# frontend_v1.net
KiCad netlist of a schematic drawn in EAGLE
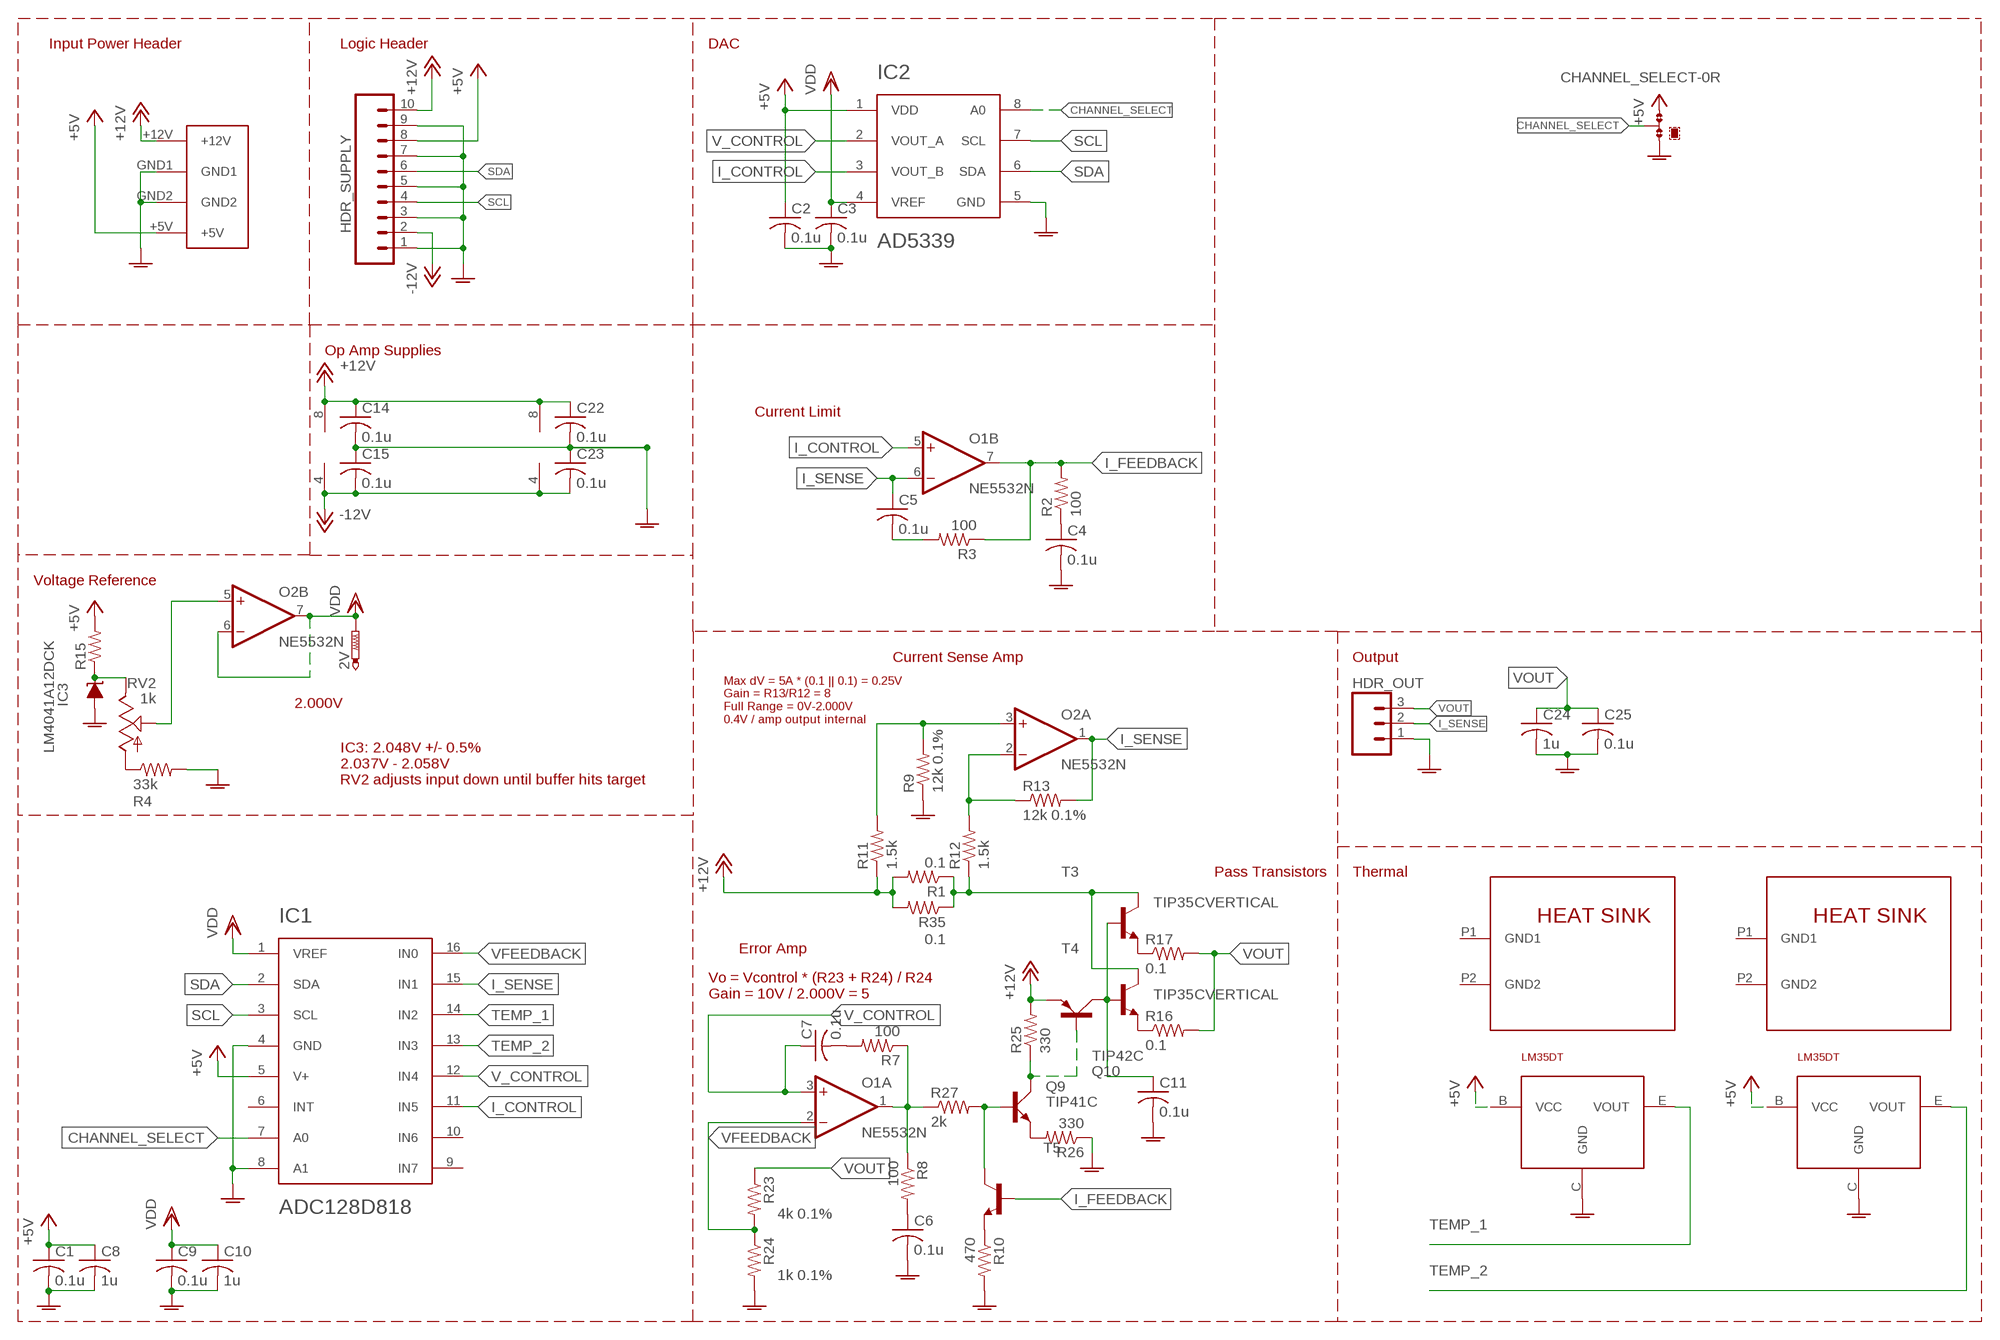
[diagram p0: schematic, sheet 1]

(export (version "E")
  (design (tool "Eeschema 10.0.6"))
  (components
    (comp (ref "2V")
      (value "PTR1PAD1-17")
      (footprint "eagle-import:P1-17")
      (libsource (lib "eagle-import") (part "PTR1PAD1-17"))
    )
    (comp (ref "C1")
      (value "0.1u")
      (footprint "eagle-import:C0805")
      (libsource (lib "eagle-import") (part "C-USC0805"))
    )
    (comp (ref "C2")
      (value "0.1u")
      (footprint "eagle-import:C0805")
      (libsource (lib "eagle-import") (part "C-USC0805"))
    )
    (comp (ref "C3")
      (value "0.1u")
      (footprint "eagle-import:C0805")
      (libsource (lib "eagle-import") (part "C-USC0805"))
    )
    (comp (ref "C4")
      (value "0.1u")
      (footprint "eagle-import:C0805")
      (libsource (lib "eagle-import") (part "C-USC0805"))
    )
    (comp (ref "C5")
      (value "0.1u")
      (footprint "eagle-import:C0805")
      (libsource (lib "eagle-import") (part "C-USC0805"))
    )
    (comp (ref "C6")
      (value "0.1u")
      (footprint "eagle-import:C0805")
      (libsource (lib "eagle-import") (part "C-USC0805"))
    )
    (comp (ref "C7")
      (value "0.1u")
      (footprint "eagle-import:C0805")
      (libsource (lib "eagle-import") (part "C-USC0805"))
    )
    (comp (ref "C8")
      (value "1u")
      (footprint "eagle-import:C0805")
      (libsource (lib "eagle-import") (part "C-USC0805"))
    )
    (comp (ref "C9")
      (value "0.1u")
      (footprint "eagle-import:C0805")
      (libsource (lib "eagle-import") (part "C-USC0805"))
    )
    (comp (ref "C10")
      (value "1u")
      (footprint "eagle-import:C0805")
      (libsource (lib "eagle-import") (part "C-USC0805"))
    )
    (comp (ref "C11")
      (value "0.1u")
      (footprint "eagle-import:C0805")
      (libsource (lib "eagle-import") (part "C-USC0805"))
    )
    (comp (ref "C14")
      (value "0.1u")
      (footprint "eagle-import:C0805")
      (libsource (lib "eagle-import") (part "C-USC0805"))
    )
    (comp (ref "C15")
      (value "0.1u")
      (footprint "eagle-import:C0805")
      (libsource (lib "eagle-import") (part "C-USC0805"))
    )
    (comp (ref "C22")
      (value "0.1u")
      (footprint "eagle-import:C0805")
      (libsource (lib "eagle-import") (part "C-USC0805"))
    )
    (comp (ref "C23")
      (value "0.1u")
      (footprint "eagle-import:C0805")
      (libsource (lib "eagle-import") (part "C-USC0805"))
    )
    (comp (ref "C24")
      (value "1u")
      (footprint "eagle-import:C1206")
      (libsource (lib "eagle-import") (part "C-USC1206"))
    )
    (comp (ref "C25")
      (value "0.1u")
      (footprint "eagle-import:C1206")
      (libsource (lib "eagle-import") (part "C-USC1206"))
    )
    (comp (ref "CHANNEL_SELECT")
      (value "0R-JUMPA")
      (footprint "eagle-import:A0R-JMP")
      (libsource (lib "eagle-import") (part "0R-JUMPA"))
    )
    (comp (ref "HDR_OUT")
      (value "M03")
      (footprint "eagle-import:03P")
      (libsource (lib "eagle-import") (part "M03"))
    )
    (comp (ref "HDR_SUPPLY")
      (value "M10")
      (footprint "eagle-import:10P")
      (libsource (lib "eagle-import") (part "M10"))
    )
    (comp (ref "IC1")
      (value "ADC128D818")
      (footprint "eagle-import:TSSOP16")
      (libsource (lib "eagle-import") (part "ADC128D818"))
    )
    (comp (ref "IC2")
      (value "AD5339MSOP8")
      (footprint "eagle-import:MSOP08")
      (libsource (lib "eagle-import") (part "AD5339MSOP8"))
    )
    (comp (ref "IC3")
      (value "LM4041A12DCK")
      (footprint "eagle-import:DCK_R-PDSO-G5")
      (fields (field (name "MPN") "LM4041A12IDCKR"))
      (libsource (lib "eagle-import") (part "LM4041DCKA12"))
    )
    (comp (ref "O1")
      (value "NE5532N")
      (footprint "eagle-import:DIL08")
      (libsource (lib "eagle-import") (part "NE5532N"))
    )
    (comp (ref "O2")
      (value "NE5532N")
      (footprint "eagle-import:DIL08")
      (libsource (lib "eagle-import") (part "NE5532N"))
    )
    (comp (ref "Q9")
      (value "TIP41C")
      (footprint "eagle-import:TO220AV")
      (libsource (lib "eagle-import") (part "TIP41C"))
    )
    (comp (ref "Q10")
      (value "TIP42C")
      (footprint "eagle-import:TO220AV")
      (libsource (lib "eagle-import") (part "TIP42C"))
    )
    (comp (ref "R1")
      (value "0.1")
      (footprint "eagle-import:R2512")
      (libsource (lib "eagle-import") (part "R-US_R2512"))
    )
    (comp (ref "R2")
      (value "100")
      (footprint "eagle-import:M0805")
      (libsource (lib "eagle-import") (part "R-US_M0805"))
    )
    (comp (ref "R3")
      (value "100")
      (footprint "eagle-import:M0805")
      (libsource (lib "eagle-import") (part "R-US_M0805"))
    )
    (comp (ref "R4")
      (value "33k")
      (footprint "eagle-import:M0805")
      (libsource (lib "eagle-import") (part "R-US_M0805"))
    )
    (comp (ref "R7")
      (value "100")
      (footprint "eagle-import:M0805")
      (libsource (lib "eagle-import") (part "R-US_M0805"))
    )
    (comp (ref "R8")
      (value "100")
      (footprint "eagle-import:M0805")
      (libsource (lib "eagle-import") (part "R-US_M0805"))
    )
    (comp (ref "R9")
      (value "12k 0.1%")
      (footprint "eagle-import:M0805")
      (libsource (lib "eagle-import") (part "R-US_M0805"))
    )
    (comp (ref "R10")
      (value "470")
      (footprint "eagle-import:M0805")
      (libsource (lib "eagle-import") (part "R-US_M0805"))
    )
    (comp (ref "R11")
      (value "1.5k")
      (footprint "eagle-import:M0805")
      (libsource (lib "eagle-import") (part "R-US_M0805"))
    )
    (comp (ref "R12")
      (value "1.5k")
      (footprint "eagle-import:M0805")
      (libsource (lib "eagle-import") (part "R-US_M0805"))
    )
    (comp (ref "R13")
      (value "12k 0.1%")
      (footprint "eagle-import:M0805")
      (libsource (lib "eagle-import") (part "R-US_M0805"))
    )
    (comp (ref "R15")
      (value "R-US_M0805")
      (footprint "eagle-import:M0805")
      (libsource (lib "eagle-import") (part "R-US_M0805"))
    )
    (comp (ref "R16")
      (value "0.1")
      (footprint "eagle-import:R2512")
      (libsource (lib "eagle-import") (part "R-US_R2512"))
    )
    (comp (ref "R17")
      (value "0.1")
      (footprint "eagle-import:R2512")
      (libsource (lib "eagle-import") (part "R-US_R2512"))
    )
    (comp (ref "R23")
      (value "4k 0.1%")
      (footprint "eagle-import:M0805")
      (libsource (lib "eagle-import") (part "R-US_M0805"))
    )
    (comp (ref "R24")
      (value "1k 0.1%")
      (footprint "eagle-import:M0805")
      (libsource (lib "eagle-import") (part "R-US_M0805"))
    )
    (comp (ref "R25")
      (value "330")
      (footprint "eagle-import:M0805")
      (libsource (lib "eagle-import") (part "R-US_M0805"))
    )
    (comp (ref "R26")
      (value "330")
      (footprint "eagle-import:M0805")
      (libsource (lib "eagle-import") (part "R-US_M0805"))
    )
    (comp (ref "R27")
      (value "2k")
      (footprint "eagle-import:M0805")
      (libsource (lib "eagle-import") (part "R-US_M0805"))
    )
    (comp (ref "R35")
      (value "0.1")
      (footprint "eagle-import:R2512")
      (libsource (lib "eagle-import") (part "R-US_R2512"))
    )
    (comp (ref "RV2")
      (value "1k")
      (footprint "eagle-import:TRIM_POT")
      (libsource (lib "eagle-import") (part "POTTRIM"))
    )
    (comp (ref "T3")
      (value "TIP35CVERTICAL")
      (footprint "eagle-import:TO247")
      (libsource (lib "eagle-import") (part "TIP35CVERTICAL"))
    )
    (comp (ref "T4")
      (value "TIP35CVERTICAL")
      (footprint "eagle-import:TO247")
      (libsource (lib "eagle-import") (part "TIP35CVERTICAL"))
    )
    (comp (ref "T5")
      (value "MMBT2222ALT1-NPN-SOT23-BEC")
      (footprint "eagle-import:SOT23-BEC")
      (libsource (lib "eagle-import") (part "-NPN-SOT23-BECMMBT2222ALT1"))
    )
    (comp (ref "U$1")
      (value "MOLEX-8981")
      (footprint "eagle-import:MOLEX-8981-MALE")
      (libsource (lib "eagle-import") (part "MOLEX-8981"))
    )
    (comp (ref "U$2")
      (value "FA-T220-X")
      (footprint "eagle-import:FA-T220-X")
      (libsource (lib "eagle-import") (part "FA-T220-X"))
    )
    (comp (ref "U$3")
      (value "FA-T220-X")
      (footprint "eagle-import:FA-T220-X")
      (libsource (lib "eagle-import") (part "FA-T220-X"))
    )
    (comp (ref "U2")
      (value "LM35DT")
      (footprint "eagle-import:TO220AV")
      (libsource (lib "eagle-import") (part "LM35DT"))
    )
    (comp (ref "U3")
      (value "LM35DT")
      (footprint "eagle-import:TO220AV")
      (libsource (lib "eagle-import") (part "LM35DT"))
    )
  )
  (nets
    (net (code "1") (name "+5V") (class "Default")
      (node (ref "C1") (pin "1") (pinfunction "1_1") (pintype "passive"))
      (node (ref "C2") (pin "1") (pinfunction "1_1") (pintype "passive"))
      (node (ref "C8") (pin "1") (pinfunction "1_1") (pintype "passive"))
      (node (ref "CHANNEL_SELECT") (pin "3") (pinfunction "3_3") (pintype "passive"))
      (node (ref "HDR_SUPPLY") (pin "8") (pinfunction "8_8") (pintype "passive"))
      (node (ref "IC1") (pin "5") (pinfunction "V+_5") (pintype "bidirectional"))
      (node (ref "IC2") (pin "1") (pinfunction "VDD_1") (pintype "bidirectional"))
      (node (ref "R15") (pin "2") (pinfunction "2_2") (pintype "passive"))
      (node (ref "U$1") (pin "+5V") (pinfunction "+5V_+5V") (pintype "bidirectional"))
      (node (ref "U2") (pin "B") (pinfunction "VCC_B") (pintype "bidirectional"))
      (node (ref "U3") (pin "B") (pinfunction "VCC_B") (pintype "bidirectional"))
    )
    (net (code "2") (name "+12V") (class "Default")
      (node (ref "C14") (pin "1") (pinfunction "1_1") (pintype "passive"))
      (node (ref "C22") (pin "1") (pinfunction "1_1") (pintype "passive"))
      (node (ref "HDR_SUPPLY") (pin "10") (pinfunction "10_10") (pintype "passive"))
      (node (ref "O1") (pin "8") (pinfunction "V+_8") (pintype "power_in"))
      (node (ref "O2") (pin "8") (pinfunction "V+_8") (pintype "power_in"))
      (node (ref "Q10") (pin "E") (pinfunction "E_E") (pintype "passive"))
      (node (ref "R1") (pin "2") (pinfunction "2_2") (pintype "passive"))
      (node (ref "R11") (pin "1") (pinfunction "1_1") (pintype "passive"))
      (node (ref "R25") (pin "2") (pinfunction "2_2") (pintype "passive"))
      (node (ref "R35") (pin "2") (pinfunction "2_2") (pintype "passive"))
      (node (ref "U$1") (pin "+12V") (pinfunction "+12V_+12V") (pintype "bidirectional"))
    )
    (net (code "3") (name "-12V") (class "Default")
      (node (ref "C15") (pin "2") (pinfunction "2_2") (pintype "passive"))
      (node (ref "C23") (pin "2") (pinfunction "2_2") (pintype "passive"))
      (node (ref "HDR_SUPPLY") (pin "2") (pinfunction "2_2") (pintype "passive"))
      (node (ref "O1") (pin "4") (pinfunction "V-_4") (pintype "power_in"))
      (node (ref "O2") (pin "4") (pinfunction "V-_4") (pintype "power_in"))
    )
    (net (code "4") (name "CHANNEL_SELECT") (class "Default")
      (node (ref "CHANNEL_SELECT") (pin "2") (pinfunction "2_2") (pintype "passive"))
      (node (ref "IC1") (pin "7") (pinfunction "A0_7") (pintype "bidirectional"))
      (node (ref "IC2") (pin "8") (pinfunction "A0_8") (pintype "bidirectional"))
    )
    (net (code "5") (name "GNDA") (class "Default")
      (node (ref "C1") (pin "2") (pinfunction "2_2") (pintype "passive"))
      (node (ref "C10") (pin "2") (pinfunction "2_2") (pintype "passive"))
      (node (ref "C11") (pin "2") (pinfunction "2_2") (pintype "passive"))
      (node (ref "C14") (pin "2") (pinfunction "2_2") (pintype "passive"))
      (node (ref "C15") (pin "1") (pinfunction "1_1") (pintype "passive"))
      (node (ref "C2") (pin "2") (pinfunction "2_2") (pintype "passive"))
      (node (ref "C22") (pin "2") (pinfunction "2_2") (pintype "passive"))
      (node (ref "C23") (pin "1") (pinfunction "1_1") (pintype "passive"))
      (node (ref "C24") (pin "2") (pinfunction "2_2") (pintype "passive"))
      (node (ref "C25") (pin "2") (pinfunction "2_2") (pintype "passive"))
      (node (ref "C3") (pin "2") (pinfunction "2_2") (pintype "passive"))
      (node (ref "C4") (pin "2") (pinfunction "2_2") (pintype "passive"))
      (node (ref "C6") (pin "2") (pinfunction "2_2") (pintype "passive"))
      (node (ref "C8") (pin "2") (pinfunction "2_2") (pintype "passive"))
      (node (ref "C9") (pin "2") (pinfunction "2_2") (pintype "passive"))
      (node (ref "CHANNEL_SELECT") (pin "1") (pinfunction "1_1") (pintype "passive"))
      (node (ref "HDR_OUT") (pin "1") (pinfunction "1_1") (pintype "passive"))
      (node (ref "HDR_SUPPLY") (pin "1") (pinfunction "1_1") (pintype "passive"))
      (node (ref "HDR_SUPPLY") (pin "3") (pinfunction "3_3") (pintype "passive"))
      (node (ref "HDR_SUPPLY") (pin "5") (pinfunction "5_5") (pintype "passive"))
      (node (ref "HDR_SUPPLY") (pin "7") (pinfunction "7_7") (pintype "passive"))
      (node (ref "HDR_SUPPLY") (pin "9") (pinfunction "9_9") (pintype "passive"))
      (node (ref "IC1") (pin "4") (pinfunction "GND_4") (pintype "bidirectional"))
      (node (ref "IC1") (pin "8") (pinfunction "A1_8") (pintype "bidirectional"))
      (node (ref "IC2") (pin "5") (pinfunction "GND_5") (pintype "bidirectional"))
      (node (ref "IC3") (pin "1") (pinfunction "A_1") (pintype "passive"))
      (node (ref "R10") (pin "2") (pinfunction "2_2") (pintype "passive"))
      (node (ref "R24") (pin "2") (pinfunction "2_2") (pintype "passive"))
      (node (ref "R26") (pin "1") (pinfunction "1_1") (pintype "passive"))
      (node (ref "R4") (pin "2") (pinfunction "2_2") (pintype "passive"))
      (node (ref "R9") (pin "1") (pinfunction "1_1") (pintype "passive"))
      (node (ref "U$1") (pin "GND1") (pinfunction "GND1_GND1") (pintype "bidirectional"))
      (node (ref "U$1") (pin "GND2") (pinfunction "GND2_GND2") (pintype "bidirectional"))
      (node (ref "U2") (pin "C") (pinfunction "GND_C") (pintype "bidirectional"))
      (node (ref "U3") (pin "C") (pinfunction "GND_C") (pintype "bidirectional"))
    )
    (net (code "6") (name "I_CONTROL") (class "Default")
      (node (ref "IC1") (pin "11") (pinfunction "IN5_11") (pintype "bidirectional"))
      (node (ref "IC2") (pin "3") (pinfunction "VOUT_B_3") (pintype "bidirectional"))
      (node (ref "O1") (pin "5") (pinfunction "+IN_5") (pintype "input"))
    )
    (net (code "7") (name "I_FEEDBACK") (class "Default")
      (node (ref "O1") (pin "7") (pinfunction "OUT_7") (pintype "output"))
      (node (ref "R2") (pin "2") (pinfunction "2_2") (pintype "passive"))
      (node (ref "R3") (pin "1") (pinfunction "1_1") (pintype "passive"))
      (node (ref "T5") (pin "B") (pinfunction "B_B") (pintype "passive"))
    )
    (net (code "8") (name "I_SENSE") (class "Default")
      (node (ref "C5") (pin "1") (pinfunction "1_1") (pintype "passive"))
      (node (ref "HDR_OUT") (pin "2") (pinfunction "2_2") (pintype "passive"))
      (node (ref "IC1") (pin "15") (pinfunction "IN1_15") (pintype "bidirectional"))
      (node (ref "O1") (pin "6") (pinfunction "-IN_6") (pintype "input"))
      (node (ref "O2") (pin "1") (pinfunction "OUT_1") (pintype "output"))
      (node (ref "R13") (pin "2") (pinfunction "2_2") (pintype "passive"))
    )
    (net (code "9") (name "Net-(C4-Pad1)") (class "Default")
      (node (ref "C4") (pin "1") (pinfunction "1_1") (pintype "passive"))
      (node (ref "R2") (pin "1") (pinfunction "1_1") (pintype "passive"))
    )
    (net (code "10") (name "Net-(C5-Pad2)") (class "Default")
      (node (ref "C5") (pin "2") (pinfunction "2_2") (pintype "passive"))
      (node (ref "R3") (pin "2") (pinfunction "2_2") (pintype "passive"))
    )
    (net (code "11") (name "Net-(C6-Pad1)") (class "Default")
      (node (ref "C6") (pin "1") (pinfunction "1_1") (pintype "passive"))
      (node (ref "R8") (pin "2") (pinfunction "2_2") (pintype "passive"))
    )
    (net (code "12") (name "Net-(C7-Pad2)") (class "Default")
      (node (ref "C7") (pin "2") (pinfunction "2_2") (pintype "passive"))
      (node (ref "R7") (pin "2") (pinfunction "2_2") (pintype "passive"))
    )
    (net (code "13") (name "Net-(IC3-C)") (class "Default")
      (node (ref "IC3") (pin "3") (pinfunction "C_3") (pintype "passive"))
      (node (ref "R15") (pin "1") (pinfunction "1_1") (pintype "passive"))
      (node (ref "RV2") (pin "2") (pinfunction "E_2") (pintype "passive"))
    )
    (net (code "14") (name "Net-(O1A-OUT)") (class "Default")
      (node (ref "O1") (pin "1") (pinfunction "OUT_1") (pintype "output"))
      (node (ref "R27") (pin "1") (pinfunction "1_1") (pintype "passive"))
      (node (ref "R7") (pin "1") (pinfunction "1_1") (pintype "passive"))
      (node (ref "R8") (pin "1") (pinfunction "1_1") (pintype "passive"))
    )
    (net (code "15") (name "Net-(O2A-+IN)") (class "Default")
      (node (ref "O2") (pin "3") (pinfunction "+IN_3") (pintype "input"))
      (node (ref "R11") (pin "2") (pinfunction "2_2") (pintype "passive"))
      (node (ref "R9") (pin "2") (pinfunction "2_2") (pintype "passive"))
    )
    (net (code "16") (name "Net-(O2A--IN)") (class "Default")
      (node (ref "O2") (pin "2") (pinfunction "-IN_2") (pintype "input"))
      (node (ref "R12") (pin "2") (pinfunction "2_2") (pintype "passive"))
      (node (ref "R13") (pin "1") (pinfunction "1_1") (pintype "passive"))
    )
    (net (code "17") (name "Net-(O2B-+IN)") (class "Default")
      (node (ref "O2") (pin "5") (pinfunction "+IN_5") (pintype "input"))
      (node (ref "RV2") (pin "1") (pinfunction "S_1") (pintype "passive"))
    )
    (net (code "18") (name "Net-(Q9-PadB)") (class "Default")
      (node (ref "Q9") (pin "B") (pinfunction "B_B") (pintype "passive"))
      (node (ref "R27") (pin "2") (pinfunction "2_2") (pintype "passive"))
      (node (ref "T5") (pin "C") (pinfunction "C_C") (pintype "passive"))
    )
    (net (code "19") (name "Net-(Q9-PadE)") (class "Default")
      (node (ref "Q9") (pin "E") (pinfunction "E_E") (pintype "passive"))
      (node (ref "R26") (pin "2") (pinfunction "2_2") (pintype "passive"))
    )
    (net (code "20") (name "Net-(Q10-PadB)") (class "Default")
      (node (ref "Q10") (pin "B") (pinfunction "B_B") (pintype "passive"))
      (node (ref "Q9") (pin "C") (pinfunction "C_C") (pintype "passive"))
      (node (ref "R25") (pin "1") (pinfunction "1_1") (pintype "passive"))
    )
    (net (code "21") (name "Net-(R10-Pad1)") (class "Default")
      (node (ref "R10") (pin "1") (pinfunction "1_1") (pintype "passive"))
      (node (ref "T5") (pin "E") (pinfunction "E_E") (pintype "passive"))
    )
    (net (code "22") (name "Net-(RV2-A)") (class "Default")
      (node (ref "R4") (pin "1") (pinfunction "1_1") (pintype "passive"))
      (node (ref "RV2") (pin "3") (pinfunction "A_3") (pintype "passive"))
    )
    (net (code "23") (name "Net-(T3-B)") (class "Default")
      (node (ref "C11") (pin "1") (pinfunction "1_1") (pintype "passive"))
      (node (ref "Q10") (pin "C") (pinfunction "C_C") (pintype "passive"))
      (node (ref "T3") (pin "P1") (pinfunction "B_P1") (pintype "passive"))
      (node (ref "T4") (pin "P1") (pinfunction "B_P1") (pintype "passive"))
    )
    (net (code "24") (name "Net-(T3-C)") (class "Default")
      (node (ref "R1") (pin "1") (pinfunction "1_1") (pintype "passive"))
      (node (ref "R12") (pin "1") (pinfunction "1_1") (pintype "passive"))
      (node (ref "R35") (pin "1") (pinfunction "1_1") (pintype "passive"))
      (node (ref "T3") (pin "P2") (pinfunction "C_P2") (pintype "passive"))
      (node (ref "T4") (pin "P2") (pinfunction "C_P2") (pintype "passive"))
    )
    (net (code "25") (name "Net-(T3-E)") (class "Default")
      (node (ref "R17") (pin "1") (pinfunction "1_1") (pintype "passive"))
      (node (ref "T3") (pin "P3") (pinfunction "E_P3") (pintype "passive"))
    )
    (net (code "26") (name "Net-(T4-E)") (class "Default")
      (node (ref "R16") (pin "1") (pinfunction "1_1") (pintype "passive"))
      (node (ref "T4") (pin "P3") (pinfunction "E_P3") (pintype "passive"))
    )
    (net (code "27") (name "SCL") (class "Default")
      (node (ref "HDR_SUPPLY") (pin "4") (pinfunction "4_4") (pintype "passive"))
      (node (ref "IC1") (pin "3") (pinfunction "SCL_3") (pintype "bidirectional"))
      (node (ref "IC2") (pin "7") (pinfunction "SCL_7") (pintype "bidirectional"))
    )
    (net (code "28") (name "SDA") (class "Default")
      (node (ref "HDR_SUPPLY") (pin "6") (pinfunction "6_6") (pintype "passive"))
      (node (ref "IC1") (pin "2") (pinfunction "SDA_2") (pintype "bidirectional"))
      (node (ref "IC2") (pin "6") (pinfunction "SDA_6") (pintype "bidirectional"))
    )
    (net (code "29") (name "TEMP_1") (class "Default")
      (node (ref "IC1") (pin "14") (pinfunction "IN2_14") (pintype "bidirectional"))
      (node (ref "U2") (pin "E") (pinfunction "VOUT_E") (pintype "bidirectional"))
    )
    (net (code "30") (name "TEMP_2") (class "Default")
      (node (ref "IC1") (pin "13") (pinfunction "IN3_13") (pintype "bidirectional"))
      (node (ref "U3") (pin "E") (pinfunction "VOUT_E") (pintype "bidirectional"))
    )
    (net (code "31") (name "VDD") (class "Default")
      (node (ref "2V") (pin "TP") (pinfunction "TP_TP") (pintype "input"))
      (node (ref "C10") (pin "1") (pinfunction "1_1") (pintype "passive"))
      (node (ref "C3") (pin "1") (pinfunction "1_1") (pintype "passive"))
      (node (ref "C9") (pin "1") (pinfunction "1_1") (pintype "passive"))
      (node (ref "IC1") (pin "1") (pinfunction "VREF_1") (pintype "bidirectional"))
      (node (ref "IC2") (pin "4") (pinfunction "VREF_4") (pintype "bidirectional"))
      (node (ref "O2") (pin "6") (pinfunction "-IN_6") (pintype "input"))
      (node (ref "O2") (pin "7") (pinfunction "OUT_7") (pintype "output"))
    )
    (net (code "32") (name "VFEEDBACK") (class "Default")
      (node (ref "IC1") (pin "16") (pinfunction "IN0_16") (pintype "bidirectional"))
      (node (ref "O1") (pin "2") (pinfunction "-IN_2") (pintype "input"))
      (node (ref "R23") (pin "2") (pinfunction "2_2") (pintype "passive"))
      (node (ref "R24") (pin "1") (pinfunction "1_1") (pintype "passive"))
    )
    (net (code "33") (name "VOUT") (class "Default")
      (node (ref "C24") (pin "1") (pinfunction "1_1") (pintype "passive"))
      (node (ref "C25") (pin "1") (pinfunction "1_1") (pintype "passive"))
      (node (ref "HDR_OUT") (pin "3") (pinfunction "3_3") (pintype "passive"))
      (node (ref "R16") (pin "2") (pinfunction "2_2") (pintype "passive"))
      (node (ref "R17") (pin "2") (pinfunction "2_2") (pintype "passive"))
      (node (ref "R23") (pin "1") (pinfunction "1_1") (pintype "passive"))
    )
    (net (code "34") (name "V_CONTROL") (class "Default")
      (node (ref "C7") (pin "1") (pinfunction "1_1") (pintype "passive"))
      (node (ref "IC1") (pin "12") (pinfunction "IN4_12") (pintype "bidirectional"))
      (node (ref "IC2") (pin "2") (pinfunction "VOUT_A_2") (pintype "bidirectional"))
      (node (ref "O1") (pin "3") (pinfunction "+IN_3") (pintype "input"))
    )
    (net (code "35") (name "unconnected-(IC1-IN6-Pad10)") (class "Default")
      (node (ref "IC1") (pin "10") (pinfunction "IN6_10") (pintype "bidirectional"))
    )
    (net (code "36") (name "unconnected-(IC1-IN7-Pad9)") (class "Default")
      (node (ref "IC1") (pin "9") (pinfunction "IN7_9") (pintype "bidirectional"))
    )
    (net (code "37") (name "unconnected-(IC1-INT-Pad6)") (class "Default")
      (node (ref "IC1") (pin "6") (pinfunction "INT_6") (pintype "bidirectional"))
    )
    (net (code "38") (name "unconnected-(U$2-GND1-PadP1)") (class "Default")
      (node (ref "U$2") (pin "P1") (pinfunction "GND1_P1") (pintype "bidirectional"))
    )
    (net (code "39") (name "unconnected-(U$2-GND2-PadP2)") (class "Default")
      (node (ref "U$2") (pin "P2") (pinfunction "GND2_P2") (pintype "bidirectional"))
    )
    (net (code "40") (name "unconnected-(U$3-GND1-PadP1)") (class "Default")
      (node (ref "U$3") (pin "P1") (pinfunction "GND1_P1") (pintype "bidirectional"))
    )
    (net (code "41") (name "unconnected-(U$3-GND2-PadP2)") (class "Default")
      (node (ref "U$3") (pin "P2") (pinfunction "GND2_P2") (pintype "bidirectional"))
    )
  )
)
